# connect.net
KiCad netlist of a schematic drawn in Altium Designer
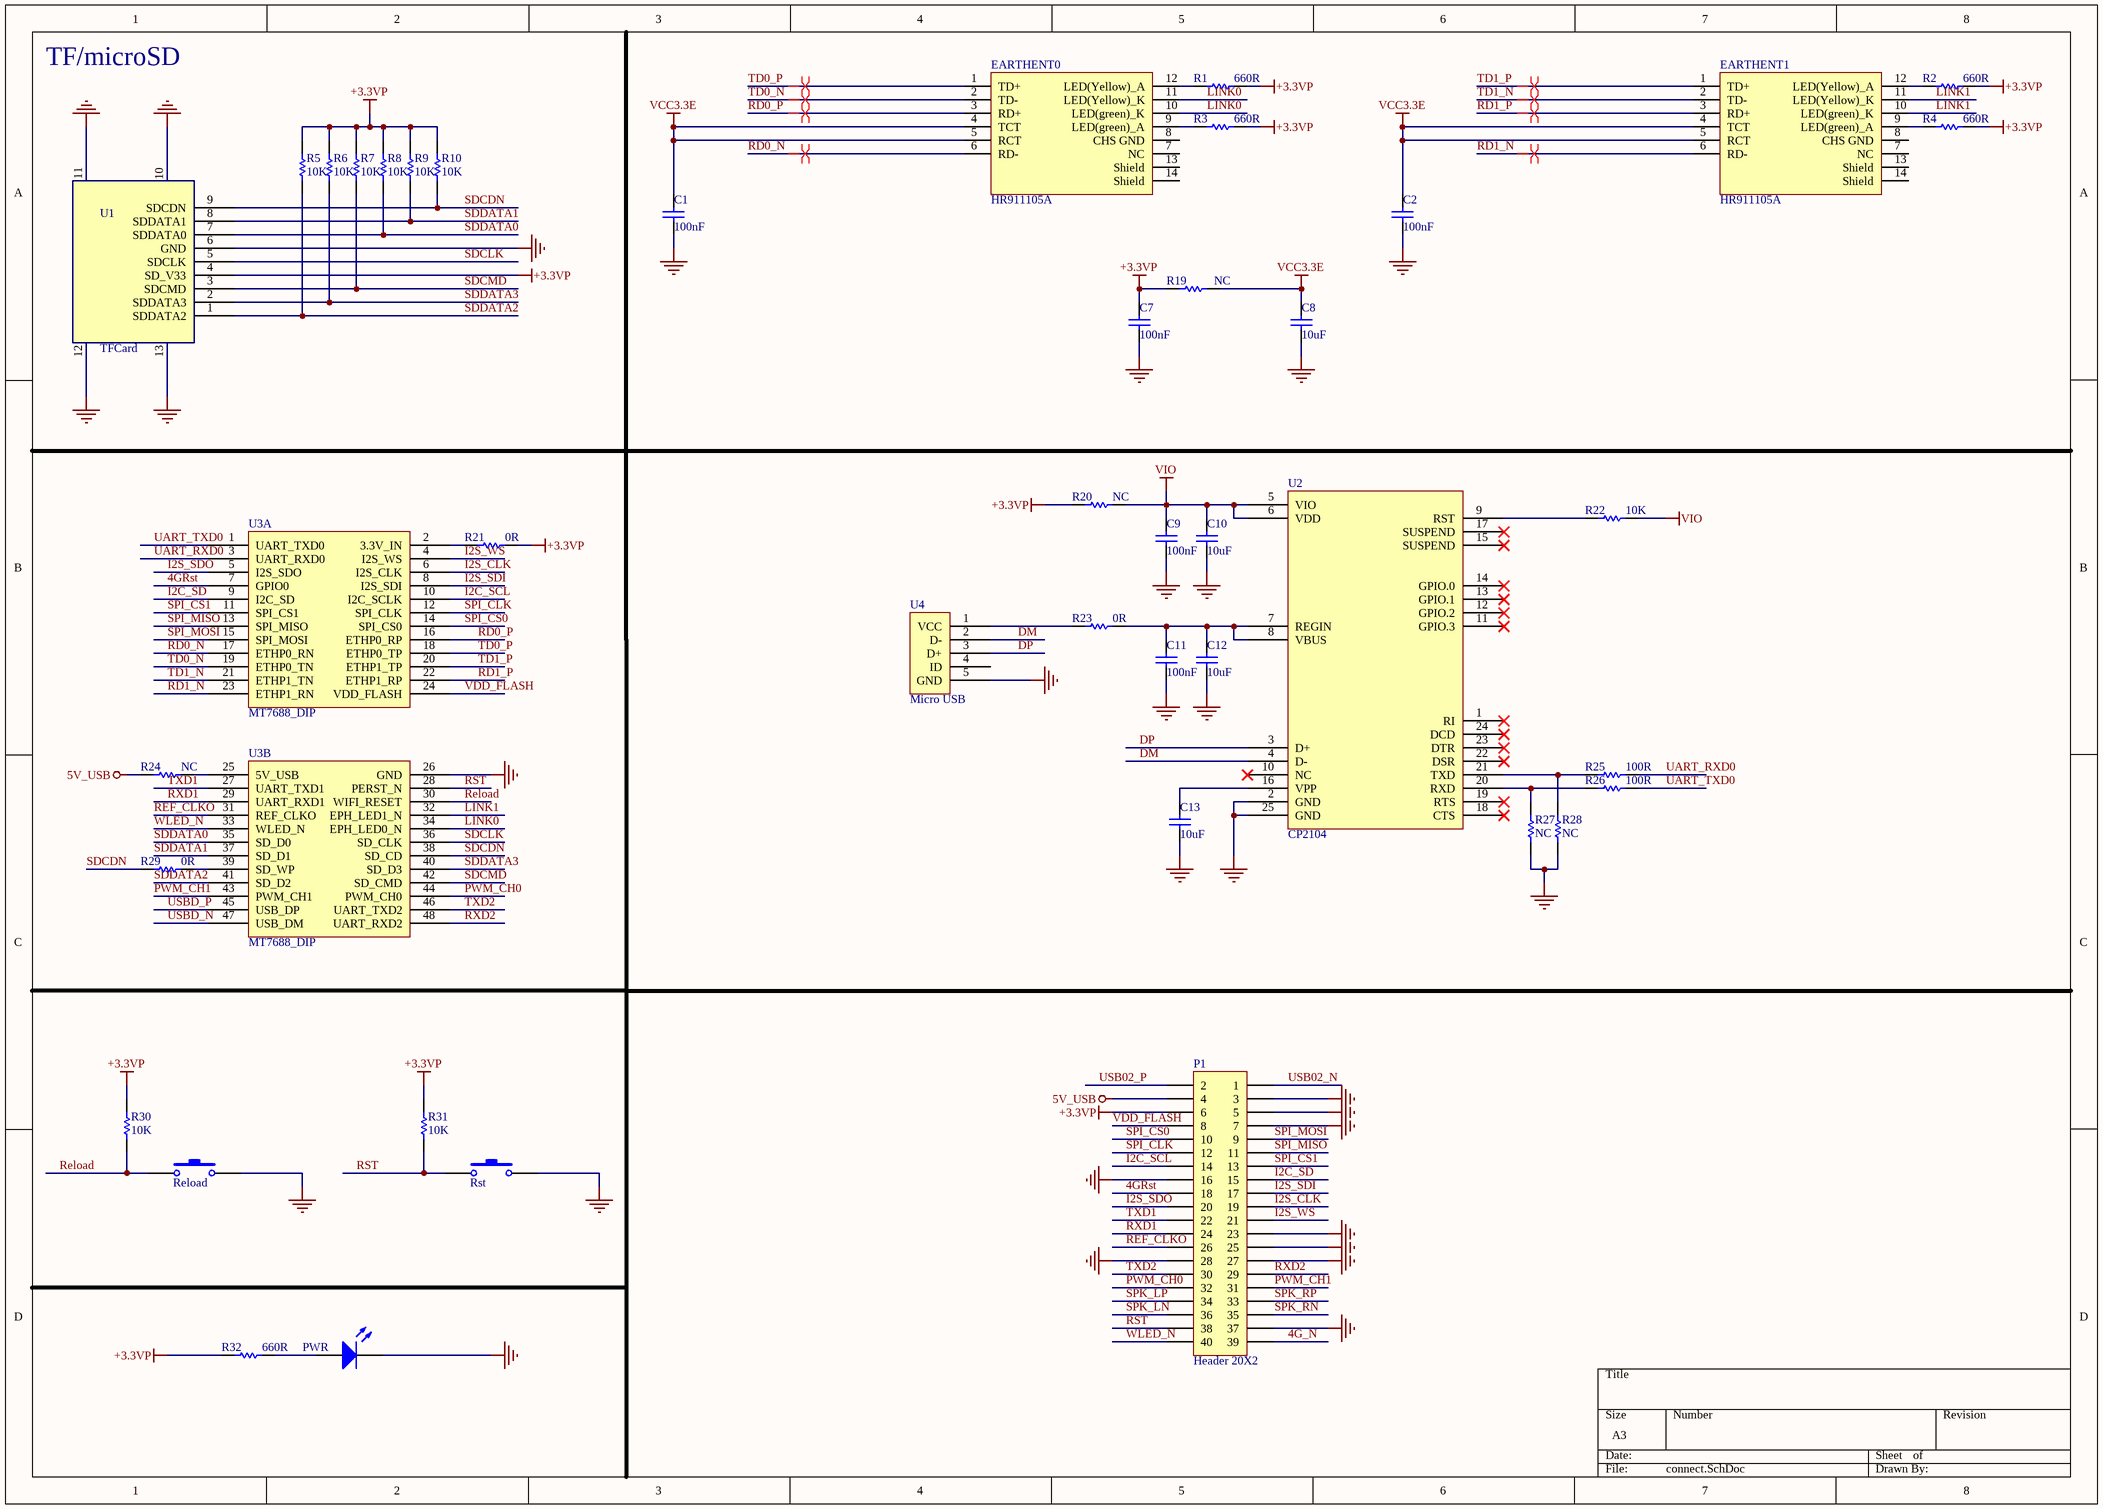
[diagram p0: connect.SchDoc]

(export (version "E")
  (design (tool "Eeschema 10.0.6"))
  (components
    (comp (ref "C1")
      (value "100nF")
      (footprint "C0603L")
      (description "Capacitor (Semiconductor SIM Model)")
      (fields (field (name "Comment") "Cap Semi") (field (name "PUBLISHER") "Altium Limited"))
      (libsource (lib "Miscellaneous Devices") (part "Cap Semi"))
    )
    (comp (ref "C2")
      (value "100nF")
      (footprint "C0603L")
      (description "Capacitor (Semiconductor SIM Model)")
      (fields (field (name "Comment") "Cap Semi") (field (name "PUBLISHER") "Altium Limited"))
      (libsource (lib "Miscellaneous Devices") (part "Cap Semi"))
    )
    (comp (ref "C7")
      (value "100nF")
      (footprint "C0603L")
      (description "Capacitor (Semiconductor SIM Model)")
      (fields (field (name "Comment") "Cap Semi") (field (name "PUBLISHER") "Altium Limited"))
      (libsource (lib "Miscellaneous Devices") (part "Cap Semi"))
    )
    (comp (ref "C8")
      (value "10uF")
      (footprint "C0603L")
      (description "Capacitor (Semiconductor SIM Model)")
      (fields (field (name "Comment") "Cap Semi") (field (name "PUBLISHER") "Altium Limited"))
      (libsource (lib "Miscellaneous Devices") (part "Cap Semi"))
    )
    (comp (ref "C9")
      (value "100nF")
      (footprint "C0603L")
      (description "Capacitor (Semiconductor SIM Model)")
      (fields (field (name "Comment") "Cap Semi") (field (name "PUBLISHER") "Altium Limited"))
      (libsource (lib "Miscellaneous Devices") (part "Cap Semi"))
    )
    (comp (ref "C10")
      (value "10uF")
      (footprint "C0603L")
      (description "Capacitor (Semiconductor SIM Model)")
      (fields (field (name "Comment") "Cap Semi") (field (name "PUBLISHER") "Altium Limited"))
      (libsource (lib "Miscellaneous Devices") (part "Cap Semi"))
    )
    (comp (ref "C11")
      (value "100nF")
      (footprint "C0603L")
      (description "Capacitor (Semiconductor SIM Model)")
      (fields (field (name "Comment") "Cap Semi") (field (name "PUBLISHER") "Altium Limited"))
      (libsource (lib "Miscellaneous Devices") (part "Cap Semi"))
    )
    (comp (ref "C12")
      (value "10uF")
      (footprint "C0603L")
      (description "Capacitor (Semiconductor SIM Model)")
      (fields (field (name "Comment") "Cap Semi") (field (name "PUBLISHER") "Altium Limited"))
      (libsource (lib "Miscellaneous Devices") (part "Cap Semi"))
    )
    (comp (ref "C13")
      (value "10uF")
      (footprint "C0603L")
      (description "Capacitor (Semiconductor SIM Model)")
      (fields (field (name "Comment") "Cap Semi") (field (name "PUBLISHER") "Altium Limited"))
      (libsource (lib "Miscellaneous Devices") (part "Cap Semi"))
    )
    (comp (ref "EARTHENT0")
      (value "HR911105A")
      (footprint "HR911105A")
      (fields (field (name "PART NUMBER") "3DZ0105115"))
      (libsource (lib "接插件") (part "HR911105A"))
    )
    (comp (ref "EARTHENT1")
      (value "HR911105A")
      (footprint "HR911105A")
      (fields (field (name "PART NUMBER") "3DZ0105115"))
      (libsource (lib "接插件") (part "HR911105A"))
    )
    (comp (ref "P1")
      (value "Header 20X2")
      (footprint "HDR2X20")
      (description "Header, 20-Pin, Dual row")
      (fields (field (name "PUBLISHER") "Altium Limited"))
      (libsource (lib "Miscellaneous Connectors") (part "Header 20X2"))
    )
    (comp (ref "PWR")
      (value "leds_0603")
      (footprint "0603LED")
      (libsource (lib "USB_SOUND") (part "leds_0603"))
    )
    (comp (ref "R1")
      (value "660R")
      (footprint "R0603L")
      (description "Semiconductor Resistor")
      (fields (field (name "Comment") "Res Semi") (field (name "PUBLISHER") "Altium Limited"))
      (libsource (lib "Miscellaneous Devices") (part "Res Semi"))
    )
    (comp (ref "R2")
      (value "660R")
      (footprint "R0603L")
      (description "Semiconductor Resistor")
      (fields (field (name "Comment") "Res Semi") (field (name "PUBLISHER") "Altium Limited"))
      (libsource (lib "Miscellaneous Devices") (part "Res Semi"))
    )
    (comp (ref "R3")
      (value "660R")
      (footprint "R0603L")
      (description "Semiconductor Resistor")
      (fields (field (name "Comment") "Res Semi") (field (name "PUBLISHER") "Altium Limited"))
      (libsource (lib "Miscellaneous Devices") (part "Res Semi"))
    )
    (comp (ref "R4")
      (value "660R")
      (footprint "R0603L")
      (description "Semiconductor Resistor")
      (fields (field (name "Comment") "Res Semi") (field (name "PUBLISHER") "Altium Limited"))
      (libsource (lib "Miscellaneous Devices") (part "Res Semi"))
    )
    (comp (ref "R5")
      (value "10K")
      (footprint "R0603L")
      (description "Semiconductor Resistor")
      (fields (field (name "Comment") "Res Semi") (field (name "PUBLISHER") "Altium Limited"))
      (libsource (lib "Miscellaneous Devices") (part "Res Semi"))
    )
    (comp (ref "R6")
      (value "10K")
      (footprint "R0603L")
      (description "Semiconductor Resistor")
      (fields (field (name "Comment") "Res Semi") (field (name "PUBLISHER") "Altium Limited"))
      (libsource (lib "Miscellaneous Devices") (part "Res Semi"))
    )
    (comp (ref "R7")
      (value "10K")
      (footprint "R0603L")
      (description "Semiconductor Resistor")
      (fields (field (name "Comment") "Res Semi") (field (name "PUBLISHER") "Altium Limited"))
      (libsource (lib "Miscellaneous Devices") (part "Res Semi"))
    )
    (comp (ref "R8")
      (value "10K")
      (footprint "R0603L")
      (description "Semiconductor Resistor")
      (fields (field (name "Comment") "Res Semi") (field (name "PUBLISHER") "Altium Limited"))
      (libsource (lib "Miscellaneous Devices") (part "Res Semi"))
    )
    (comp (ref "R9")
      (value "10K")
      (footprint "R0603L")
      (description "Semiconductor Resistor")
      (fields (field (name "Comment") "Res Semi") (field (name "PUBLISHER") "Altium Limited"))
      (libsource (lib "Miscellaneous Devices") (part "Res Semi"))
    )
    (comp (ref "R10")
      (value "10K")
      (footprint "R0603L")
      (description "Semiconductor Resistor")
      (fields (field (name "Comment") "Res Semi") (field (name "PUBLISHER") "Altium Limited"))
      (libsource (lib "Miscellaneous Devices") (part "Res Semi"))
    )
    (comp (ref "R19")
      (value "NC")
      (footprint "R0603L")
      (description "Semiconductor Resistor")
      (fields (field (name "Comment") "Res Semi") (field (name "PUBLISHER") "Altium Limited"))
      (libsource (lib "Miscellaneous Devices") (part "Res Semi"))
    )
    (comp (ref "R20")
      (value "NC")
      (footprint "R0603L")
      (description "Semiconductor Resistor")
      (fields (field (name "Comment") "Res Semi") (field (name "PUBLISHER") "Altium Limited"))
      (libsource (lib "Miscellaneous Devices") (part "Res Semi"))
    )
    (comp (ref "R21")
      (value "0R")
      (footprint "R0603L")
      (description "Semiconductor Resistor")
      (fields (field (name "Comment") "Res Semi") (field (name "PUBLISHER") "Altium Limited"))
      (libsource (lib "Miscellaneous Devices") (part "Res Semi"))
    )
    (comp (ref "R22")
      (value "10K")
      (footprint "R0603L")
      (description "Semiconductor Resistor")
      (fields (field (name "Comment") "Res Semi") (field (name "PUBLISHER") "Altium Limited"))
      (libsource (lib "Miscellaneous Devices") (part "Res Semi"))
    )
    (comp (ref "R23")
      (value "0R")
      (footprint "R0603L")
      (description "Semiconductor Resistor")
      (fields (field (name "Comment") "Res Semi") (field (name "PUBLISHER") "Altium Limited"))
      (libsource (lib "Miscellaneous Devices") (part "Res Semi"))
    )
    (comp (ref "R24")
      (value "NC")
      (footprint "R0603L")
      (description "Semiconductor Resistor")
      (fields (field (name "Comment") "Res Semi") (field (name "PUBLISHER") "Altium Limited"))
      (libsource (lib "Miscellaneous Devices") (part "Res Semi"))
    )
    (comp (ref "R25")
      (value "100R")
      (footprint "R0603L")
      (description "Semiconductor Resistor")
      (fields (field (name "Comment") "Res Semi") (field (name "PUBLISHER") "Altium Limited"))
      (libsource (lib "Miscellaneous Devices") (part "Res Semi"))
    )
    (comp (ref "R26")
      (value "100R")
      (footprint "R0603L")
      (description "Semiconductor Resistor")
      (fields (field (name "Comment") "Res Semi") (field (name "PUBLISHER") "Altium Limited"))
      (libsource (lib "Miscellaneous Devices") (part "Res Semi"))
    )
    (comp (ref "R27")
      (value "NC")
      (footprint "R0603L")
      (description "Semiconductor Resistor")
      (fields (field (name "Comment") "Res Semi") (field (name "PUBLISHER") "Altium Limited"))
      (libsource (lib "Miscellaneous Devices") (part "Res Semi"))
    )
    (comp (ref "R28")
      (value "NC")
      (footprint "R0603L")
      (description "Semiconductor Resistor")
      (fields (field (name "Comment") "Res Semi") (field (name "PUBLISHER") "Altium Limited"))
      (libsource (lib "Miscellaneous Devices") (part "Res Semi"))
    )
    (comp (ref "R29")
      (value "0R")
      (footprint "R0603L")
      (description "Semiconductor Resistor")
      (fields (field (name "Comment") "Res Semi") (field (name "PUBLISHER") "Altium Limited"))
      (libsource (lib "Miscellaneous Devices") (part "Res Semi"))
    )
    (comp (ref "R30")
      (value "10K")
      (footprint "R0603L")
      (description "Semiconductor Resistor")
      (fields (field (name "Comment") "Res Semi") (field (name "PUBLISHER") "Altium Limited"))
      (libsource (lib "Miscellaneous Devices") (part "Res Semi"))
    )
    (comp (ref "R31")
      (value "10K")
      (footprint "R0603L")
      (description "Semiconductor Resistor")
      (fields (field (name "Comment") "Res Semi") (field (name "PUBLISHER") "Altium Limited"))
      (libsource (lib "Miscellaneous Devices") (part "Res Semi"))
    )
    (comp (ref "R32")
      (value "660R")
      (footprint "R0603L")
      (description "Semiconductor Resistor")
      (fields (field (name "Comment") "Res Semi") (field (name "PUBLISHER") "Altium Limited"))
      (libsource (lib "Miscellaneous Devices") (part "Res Semi"))
    )
    (comp (ref "Reload") (value "key") (footprint "2x3SWD") (libsource (lib "USB_SOUND") (part "key")))
    (comp (ref "Rst") (value "key") (footprint "2x3SWD") (libsource (lib "USB_SOUND") (part "key")))
    (comp (ref "U1") (value "TFCard") (footprint "TFCard-1") (libsource (lib "USB_SOUND") (part "TFCard")))
    (comp (ref "U2")
      (value "CP2104")
      (footprint "QFN24_4X4")
      (libsource (lib "wooya_lib_footprint") (part "CP2104"))
    )
    (comp (ref "U3")
      (value "MT7688_DIP")
      (footprint "MT7688_DIP")
      (libsource (lib "wooya") (part "MT7688_DIP"))
    )
    (comp (ref "U4")
      (value "Micro USB")
      (footprint "USB-15B1")
      (libsource (lib "USB_SOUND") (part "USB mini-b"))
    )
  )
  (nets
    (net (code "1") (name "+3.3VP") (class "Default")
      (node (ref "C7") (pin "1") (pinfunction "1_1") (pintype "passive"))
      (node (ref "P1") (pin "6") (pinfunction "6_6") (pintype "passive"))
      (node (ref "R1") (pin "1") (pinfunction "1_1") (pintype "passive"))
      (node (ref "R10") (pin "2") (pinfunction "2_2") (pintype "passive"))
      (node (ref "R19") (pin "2") (pinfunction "2_2") (pintype "passive"))
      (node (ref "R2") (pin "1") (pinfunction "1_1") (pintype "passive"))
      (node (ref "R20") (pin "2") (pinfunction "2_2") (pintype "passive"))
      (node (ref "R21") (pin "1") (pinfunction "1_1") (pintype "passive"))
      (node (ref "R3") (pin "1") (pinfunction "1_1") (pintype "passive"))
      (node (ref "R30") (pin "2") (pinfunction "2_2") (pintype "passive"))
      (node (ref "R31") (pin "2") (pinfunction "2_2") (pintype "passive"))
      (node (ref "R32") (pin "2") (pinfunction "2_2") (pintype "passive"))
      (node (ref "R4") (pin "1") (pinfunction "1_1") (pintype "passive"))
      (node (ref "R5") (pin "2") (pinfunction "2_2") (pintype "passive"))
      (node (ref "R6") (pin "2") (pinfunction "2_2") (pintype "passive"))
      (node (ref "R7") (pin "2") (pinfunction "2_2") (pintype "passive"))
      (node (ref "R8") (pin "2") (pinfunction "2_2") (pintype "passive"))
      (node (ref "R9") (pin "2") (pinfunction "2_2") (pintype "passive"))
      (node (ref "U1") (pin "4") (pinfunction "SD_V33_4") (pintype "passive"))
    )
    (net (code "2") (name "/4GRst") (class "Default")
      (node (ref "P1") (pin "18") (pinfunction "18_18") (pintype "passive"))
      (node (ref "U3") (pin "7") (pinfunction "GPIO0_7") (pintype "passive"))
    )
    (net (code "3") (name "/4G_N") (class "Default")
      (node (ref "P1") (pin "39") (pinfunction "39_39") (pintype "passive"))
    )
    (net (code "4") (name "/DM") (class "Default")
      (node (ref "U2") (pin "4") (pinfunction "D-_4") (pintype "passive"))
      (node (ref "U4") (pin "2") (pinfunction "D-_2") (pintype "passive"))
    )
    (net (code "5") (name "/DP") (class "Default")
      (node (ref "U2") (pin "3") (pinfunction "D+_3") (pintype "passive"))
      (node (ref "U4") (pin "3") (pinfunction "D+_3") (pintype "passive"))
    )
    (net (code "6") (name "/I2C_SCL") (class "Default")
      (node (ref "P1") (pin "14") (pinfunction "14_14") (pintype "passive"))
      (node (ref "U3") (pin "10") (pinfunction "I2C_SCLK_10") (pintype "passive"))
    )
    (net (code "7") (name "/I2C_SD") (class "Default")
      (node (ref "P1") (pin "15") (pinfunction "15_15") (pintype "passive"))
      (node (ref "U3") (pin "9") (pinfunction "I2C_SD_9") (pintype "passive"))
    )
    (net (code "8") (name "/I2S_CLK") (class "Default")
      (node (ref "P1") (pin "19") (pinfunction "19_19") (pintype "passive"))
      (node (ref "U3") (pin "6") (pinfunction "I2S_CLK_6") (pintype "passive"))
    )
    (net (code "9") (name "/I2S_SDI") (class "Default")
      (node (ref "P1") (pin "17") (pinfunction "17_17") (pintype "passive"))
      (node (ref "U3") (pin "8") (pinfunction "I2S_SDI_8") (pintype "passive"))
    )
    (net (code "10") (name "/I2S_SDO") (class "Default")
      (node (ref "P1") (pin "20") (pinfunction "20_20") (pintype "passive"))
      (node (ref "U3") (pin "5") (pinfunction "I2S_SDO_5") (pintype "passive"))
    )
    (net (code "11") (name "/I2S_WS") (class "Default")
      (node (ref "P1") (pin "21") (pinfunction "21_21") (pintype "passive"))
      (node (ref "U3") (pin "4") (pinfunction "I2S_WS_4") (pintype "passive"))
    )
    (net (code "12") (name "/LINK0") (class "Default")
      (node (ref "EARTHENT0") (pin "10") (pinfunction "LED(green)_K_10") (pintype "passive"))
      (node (ref "EARTHENT0") (pin "11") (pinfunction "LED(Yellow)_K_11") (pintype "passive"))
      (node (ref "U3") (pin "34") (pinfunction "EPH_LED0_N_34") (pintype "passive"))
    )
    (net (code "13") (name "/LINK1") (class "Default")
      (node (ref "EARTHENT1") (pin "10") (pinfunction "LED(green)_K_10") (pintype "passive"))
      (node (ref "EARTHENT1") (pin "11") (pinfunction "LED(Yellow)_K_11") (pintype "passive"))
      (node (ref "U3") (pin "32") (pinfunction "EPH_LED1_N_32") (pintype "passive"))
    )
    (net (code "14") (name "/PWM_CH0") (class "Default")
      (node (ref "P1") (pin "32") (pinfunction "32_32") (pintype "passive"))
      (node (ref "U3") (pin "44") (pinfunction "PWM_CH0_44") (pintype "passive"))
    )
    (net (code "15") (name "/PWM_CH1") (class "Default")
      (node (ref "P1") (pin "31") (pinfunction "31_31") (pintype "passive"))
      (node (ref "U3") (pin "43") (pinfunction "PWM_CH1_43") (pintype "passive"))
    )
    (net (code "16") (name "/RD0_N") (class "Default")
      (node (ref "EARTHENT0") (pin "6") (pinfunction "RD-_6") (pintype "passive"))
      (node (ref "U3") (pin "17") (pinfunction "ETHP0_RN_17") (pintype "passive"))
    )
    (net (code "17") (name "/RD0_P") (class "Default")
      (node (ref "EARTHENT0") (pin "3") (pinfunction "RD+_3") (pintype "passive"))
      (node (ref "U3") (pin "16") (pinfunction "ETHP0_RP_16") (pintype "passive"))
    )
    (net (code "18") (name "/RD1_N") (class "Default")
      (node (ref "EARTHENT1") (pin "6") (pinfunction "RD-_6") (pintype "passive"))
      (node (ref "U3") (pin "23") (pinfunction "ETHP1_RN_23") (pintype "passive"))
    )
    (net (code "19") (name "/RD1_P") (class "Default")
      (node (ref "EARTHENT1") (pin "3") (pinfunction "RD+_3") (pintype "passive"))
      (node (ref "U3") (pin "22") (pinfunction "ETHP1_RP_22") (pintype "passive"))
    )
    (net (code "20") (name "/REF_CLKO") (class "Default")
      (node (ref "P1") (pin "26") (pinfunction "26_26") (pintype "passive"))
      (node (ref "U3") (pin "31") (pinfunction "REF_CLKO_31") (pintype "passive"))
    )
    (net (code "21") (name "/RST") (class "Default")
      (node (ref "P1") (pin "38") (pinfunction "38_38") (pintype "passive"))
      (node (ref "R31") (pin "1") (pinfunction "1_1") (pintype "passive"))
      (node (ref "Rst") (pin "2") (pinfunction "2_2") (pintype "passive"))
      (node (ref "U3") (pin "28") (pinfunction "PERST_N_28") (pintype "passive"))
    )
    (net (code "22") (name "/RXD1") (class "Default")
      (node (ref "P1") (pin "24") (pinfunction "24_24") (pintype "passive"))
      (node (ref "U3") (pin "29") (pinfunction "UART_RXD1_29") (pintype "passive"))
    )
    (net (code "23") (name "/RXD2") (class "Default")
      (node (ref "P1") (pin "29") (pinfunction "29_29") (pintype "passive"))
      (node (ref "U3") (pin "48") (pinfunction "UART_RXD2_48") (pintype "passive"))
    )
    (net (code "24") (name "/Reload") (class "Default")
      (node (ref "R30") (pin "1") (pinfunction "1_1") (pintype "passive"))
      (node (ref "Reload") (pin "2") (pinfunction "2_2") (pintype "passive"))
      (node (ref "U3") (pin "30") (pinfunction "WIFI_RESET_30") (pintype "passive"))
    )
    (net (code "25") (name "/SDCDN") (class "Default")
      (node (ref "R10") (pin "1") (pinfunction "1_1") (pintype "passive"))
      (node (ref "R29") (pin "2") (pinfunction "2_2") (pintype "passive"))
      (node (ref "U1") (pin "9") (pinfunction "SDCDN_9") (pintype "passive"))
      (node (ref "U3") (pin "38") (pinfunction "SD_CD_38") (pintype "passive"))
    )
    (net (code "26") (name "/SDCLK") (class "Default")
      (node (ref "U1") (pin "5") (pinfunction "SDCLK_5") (pintype "passive"))
      (node (ref "U3") (pin "36") (pinfunction "SD_CLK_36") (pintype "passive"))
    )
    (net (code "27") (name "/SDCMD") (class "Default")
      (node (ref "R7") (pin "1") (pinfunction "1_1") (pintype "passive"))
      (node (ref "U1") (pin "3") (pinfunction "SDCMD_3") (pintype "passive"))
      (node (ref "U3") (pin "42") (pinfunction "SD_CMD_42") (pintype "passive"))
    )
    (net (code "28") (name "/SDDATA0") (class "Default")
      (node (ref "R8") (pin "1") (pinfunction "1_1") (pintype "passive"))
      (node (ref "U1") (pin "7") (pinfunction "SDDATA0_7") (pintype "passive"))
      (node (ref "U3") (pin "35") (pinfunction "SD_D0_35") (pintype "passive"))
    )
    (net (code "29") (name "/SDDATA1") (class "Default")
      (node (ref "R9") (pin "1") (pinfunction "1_1") (pintype "passive"))
      (node (ref "U1") (pin "8") (pinfunction "SDDATA1_8") (pintype "passive"))
      (node (ref "U3") (pin "37") (pinfunction "SD_D1_37") (pintype "passive"))
    )
    (net (code "30") (name "/SDDATA2") (class "Default")
      (node (ref "R5") (pin "1") (pinfunction "1_1") (pintype "passive"))
      (node (ref "U1") (pin "1") (pinfunction "SDDATA2_1") (pintype "passive"))
      (node (ref "U3") (pin "41") (pinfunction "SD_D2_41") (pintype "passive"))
    )
    (net (code "31") (name "/SDDATA3") (class "Default")
      (node (ref "R6") (pin "1") (pinfunction "1_1") (pintype "passive"))
      (node (ref "U1") (pin "2") (pinfunction "SDDATA3_2") (pintype "passive"))
      (node (ref "U3") (pin "40") (pinfunction "SD_D3_40") (pintype "passive"))
    )
    (net (code "32") (name "/SPI_CLK") (class "Default")
      (node (ref "P1") (pin "12") (pinfunction "12_12") (pintype "passive"))
      (node (ref "U3") (pin "12") (pinfunction "SPI_CLK_12") (pintype "passive"))
    )
    (net (code "33") (name "/SPI_CS0") (class "Default")
      (node (ref "P1") (pin "10") (pinfunction "10_10") (pintype "passive"))
      (node (ref "U3") (pin "14") (pinfunction "SPI_CS0_14") (pintype "passive"))
    )
    (net (code "34") (name "/SPI_CS1") (class "Default")
      (node (ref "P1") (pin "13") (pinfunction "13_13") (pintype "passive"))
      (node (ref "U3") (pin "11") (pinfunction "SPI_CS1_11") (pintype "passive"))
    )
    (net (code "35") (name "/SPI_MISO") (class "Default")
      (node (ref "P1") (pin "11") (pinfunction "11_11") (pintype "passive"))
      (node (ref "U3") (pin "13") (pinfunction "SPI_MISO_13") (pintype "passive"))
    )
    (net (code "36") (name "/SPI_MOSI") (class "Default")
      (node (ref "P1") (pin "9") (pinfunction "9_9") (pintype "passive"))
      (node (ref "U3") (pin "15") (pinfunction "SPI_MOSI_15") (pintype "passive"))
    )
    (net (code "37") (name "/SPK_LN") (class "Default")
      (node (ref "P1") (pin "36") (pinfunction "36_36") (pintype "passive"))
    )
    (net (code "38") (name "/SPK_LP") (class "Default")
      (node (ref "P1") (pin "34") (pinfunction "34_34") (pintype "passive"))
    )
    (net (code "39") (name "/SPK_RN") (class "Default")
      (node (ref "P1") (pin "35") (pinfunction "35_35") (pintype "passive"))
    )
    (net (code "40") (name "/SPK_RP") (class "Default")
      (node (ref "P1") (pin "33") (pinfunction "33_33") (pintype "passive"))
    )
    (net (code "41") (name "/TD0_N") (class "Default")
      (node (ref "EARTHENT0") (pin "2") (pinfunction "TD-_2") (pintype "passive"))
      (node (ref "U3") (pin "19") (pinfunction "ETHP0_TN_19") (pintype "passive"))
    )
    (net (code "42") (name "/TD0_P") (class "Default")
      (node (ref "EARTHENT0") (pin "1") (pinfunction "TD+_1") (pintype "passive"))
      (node (ref "U3") (pin "18") (pinfunction "ETHP0_TP_18") (pintype "passive"))
    )
    (net (code "43") (name "/TD1_N") (class "Default")
      (node (ref "EARTHENT1") (pin "2") (pinfunction "TD-_2") (pintype "passive"))
      (node (ref "U3") (pin "21") (pinfunction "ETHP1_TN_21") (pintype "passive"))
    )
    (net (code "44") (name "/TD1_P") (class "Default")
      (node (ref "EARTHENT1") (pin "1") (pinfunction "TD+_1") (pintype "passive"))
      (node (ref "U3") (pin "20") (pinfunction "ETHP1_TP_20") (pintype "passive"))
    )
    (net (code "45") (name "/TXD1") (class "Default")
      (node (ref "P1") (pin "22") (pinfunction "22_22") (pintype "passive"))
      (node (ref "U3") (pin "27") (pinfunction "UART_TXD1_27") (pintype "passive"))
    )
    (net (code "46") (name "/TXD2") (class "Default")
      (node (ref "P1") (pin "30") (pinfunction "30_30") (pintype "passive"))
      (node (ref "U3") (pin "46") (pinfunction "UART_TXD2_46") (pintype "passive"))
    )
    (net (code "47") (name "/UART_RXD0") (class "Default")
      (node (ref "R25") (pin "1") (pinfunction "1_1") (pintype "passive"))
      (node (ref "U3") (pin "3") (pinfunction "UART_RXD0_3") (pintype "passive"))
    )
    (net (code "48") (name "/UART_TXD0") (class "Default")
      (node (ref "R26") (pin "1") (pinfunction "1_1") (pintype "passive"))
      (node (ref "U3") (pin "1") (pinfunction "UART_TXD0_1") (pintype "passive"))
    )
    (net (code "49") (name "/USB02_N") (class "Default")
      (node (ref "P1") (pin "1") (pinfunction "1_1") (pintype "passive"))
    )
    (net (code "50") (name "/USB02_P") (class "Default")
      (node (ref "P1") (pin "2") (pinfunction "2_2") (pintype "passive"))
    )
    (net (code "51") (name "/USBD_N") (class "Default")
      (node (ref "U3") (pin "47") (pinfunction "USB_DM_47") (pintype "passive"))
    )
    (net (code "52") (name "/USBD_P") (class "Default")
      (node (ref "U3") (pin "45") (pinfunction "USB_DP_45") (pintype "passive"))
    )
    (net (code "53") (name "/VDD_FLASH") (class "Default")
      (node (ref "P1") (pin "8") (pinfunction "8_8") (pintype "passive"))
      (node (ref "U3") (pin "24") (pinfunction "VDD_FLASH_24") (pintype "passive"))
    )
    (net (code "54") (name "/WLED_N") (class "Default")
      (node (ref "P1") (pin "40") (pinfunction "40_40") (pintype "passive"))
      (node (ref "U3") (pin "33") (pinfunction "WLED_N_33") (pintype "passive"))
    )
    (net (code "55") (name "5V_USB") (class "Default")
      (node (ref "P1") (pin "4") (pinfunction "4_4") (pintype "passive"))
      (node (ref "R24") (pin "2") (pinfunction "2_2") (pintype "passive"))
    )
    (net (code "56") (name "GND") (class "Default")
      (node (ref "C1") (pin "2") (pinfunction "2_2") (pintype "passive"))
      (node (ref "C10") (pin "2") (pinfunction "2_2") (pintype "passive"))
      (node (ref "C11") (pin "2") (pinfunction "2_2") (pintype "passive"))
      (node (ref "C12") (pin "2") (pinfunction "2_2") (pintype "passive"))
      (node (ref "C13") (pin "2") (pinfunction "2_2") (pintype "passive"))
      (node (ref "C2") (pin "2") (pinfunction "2_2") (pintype "passive"))
      (node (ref "C7") (pin "2") (pinfunction "2_2") (pintype "passive"))
      (node (ref "C8") (pin "2") (pinfunction "2_2") (pintype "passive"))
      (node (ref "C9") (pin "2") (pinfunction "2_2") (pintype "passive"))
      (node (ref "P1") (pin "16") (pinfunction "16_16") (pintype "passive"))
      (node (ref "P1") (pin "23") (pinfunction "23_23") (pintype "passive"))
      (node (ref "P1") (pin "25") (pinfunction "25_25") (pintype "passive"))
      (node (ref "P1") (pin "27") (pinfunction "27_27") (pintype "passive"))
      (node (ref "P1") (pin "28") (pinfunction "28_28") (pintype "passive"))
      (node (ref "P1") (pin "3") (pinfunction "3_3") (pintype "passive"))
      (node (ref "P1") (pin "37") (pinfunction "37_37") (pintype "passive"))
      (node (ref "P1") (pin "5") (pinfunction "5_5") (pintype "passive"))
      (node (ref "P1") (pin "7") (pinfunction "7_7") (pintype "passive"))
      (node (ref "PWR") (pin "2") (pinfunction "K_2") (pintype "passive"))
      (node (ref "R27") (pin "2") (pinfunction "2_2") (pintype "passive"))
      (node (ref "R28") (pin "2") (pinfunction "2_2") (pintype "passive"))
      (node (ref "Reload") (pin "1") (pinfunction "1_1") (pintype "passive"))
      (node (ref "Rst") (pin "1") (pinfunction "1_1") (pintype "passive"))
      (node (ref "U1") (pin "10") (pinfunction "10_10") (pintype "passive"))
      (node (ref "U1") (pin "11") (pinfunction "11_11") (pintype "passive"))
      (node (ref "U1") (pin "12") (pinfunction "12_12") (pintype "passive"))
      (node (ref "U1") (pin "13") (pinfunction "13_13") (pintype "passive"))
      (node (ref "U1") (pin "6") (pinfunction "GND_6") (pintype "passive"))
      (node (ref "U2") (pin "2") (pinfunction "GND_2") (pintype "passive"))
      (node (ref "U2") (pin "25") (pinfunction "GND_25") (pintype "passive"))
      (node (ref "U3") (pin "26") (pinfunction "GND_26") (pintype "passive"))
      (node (ref "U4") (pin "5") (pinfunction "GND_5") (pintype "passive"))
    )
    (net (code "57") (name "Net-(EARTHENT0-LED(Yellow)_A)") (class "Default")
      (node (ref "EARTHENT0") (pin "12") (pinfunction "LED(Yellow)_A_12") (pintype "passive"))
      (node (ref "R1") (pin "2") (pinfunction "2_2") (pintype "passive"))
    )
    (net (code "58") (name "Net-(EARTHENT0-LED(green)_A)") (class "Default")
      (node (ref "EARTHENT0") (pin "9") (pinfunction "LED(green)_A_9") (pintype "passive"))
      (node (ref "R3") (pin "2") (pinfunction "2_2") (pintype "passive"))
    )
    (net (code "59") (name "Net-(EARTHENT1-LED(Yellow)_A)") (class "Default")
      (node (ref "EARTHENT1") (pin "12") (pinfunction "LED(Yellow)_A_12") (pintype "passive"))
      (node (ref "R2") (pin "2") (pinfunction "2_2") (pintype "passive"))
    )
    (net (code "60") (name "Net-(EARTHENT1-LED(green)_A)") (class "Default")
      (node (ref "EARTHENT1") (pin "9") (pinfunction "LED(green)_A_9") (pintype "passive"))
      (node (ref "R4") (pin "2") (pinfunction "2_2") (pintype "passive"))
    )
    (net (code "61") (name "Net-(PWR-A)") (class "Default")
      (node (ref "PWR") (pin "1") (pinfunction "A_1") (pintype "passive"))
      (node (ref "R32") (pin "1") (pinfunction "1_1") (pintype "passive"))
    )
    (net (code "62") (name "Net-(U2-REGIN)") (class "Default")
      (node (ref "C11") (pin "1") (pinfunction "1_1") (pintype "passive"))
      (node (ref "C12") (pin "1") (pinfunction "1_1") (pintype "passive"))
      (node (ref "R23") (pin "1") (pinfunction "1_1") (pintype "passive"))
      (node (ref "U2") (pin "7") (pinfunction "REGIN_7") (pintype "passive"))
      (node (ref "U2") (pin "8") (pinfunction "VBUS_8") (pintype "passive"))
    )
    (net (code "63") (name "Net-(U2-RST)") (class "Default")
      (node (ref "R22") (pin "2") (pinfunction "2_2") (pintype "passive"))
      (node (ref "U2") (pin "9") (pinfunction "RST_9") (pintype "passive"))
    )
    (net (code "64") (name "Net-(U2-RXD)") (class "Default")
      (node (ref "R26") (pin "2") (pinfunction "2_2") (pintype "passive"))
      (node (ref "R27") (pin "1") (pinfunction "1_1") (pintype "passive"))
      (node (ref "U2") (pin "20") (pinfunction "RXD_20") (pintype "passive"))
    )
    (net (code "65") (name "Net-(U2-TXD)") (class "Default")
      (node (ref "R25") (pin "2") (pinfunction "2_2") (pintype "passive"))
      (node (ref "R28") (pin "1") (pinfunction "1_1") (pintype "passive"))
      (node (ref "U2") (pin "21") (pinfunction "TXD_21") (pintype "passive"))
    )
    (net (code "66") (name "Net-(U2-VPP)") (class "Default")
      (node (ref "C13") (pin "1") (pinfunction "1_1") (pintype "passive"))
      (node (ref "U2") (pin "16") (pinfunction "VPP_16") (pintype "passive"))
    )
    (net (code "67") (name "Net-(U3A-3.3V_IN)") (class "Default")
      (node (ref "R21") (pin "2") (pinfunction "2_2") (pintype "passive"))
      (node (ref "U3") (pin "2") (pinfunction "3.3V_IN_2") (pintype "passive"))
    )
    (net (code "68") (name "Net-(U3B-5V_USB)") (class "Default")
      (node (ref "R24") (pin "1") (pinfunction "1_1") (pintype "passive"))
      (node (ref "U3") (pin "25") (pinfunction "5V_USB_25") (pintype "passive"))
    )
    (net (code "69") (name "Net-(U3B-SD_WP)") (class "Default")
      (node (ref "R29") (pin "1") (pinfunction "1_1") (pintype "passive"))
      (node (ref "U3") (pin "39") (pinfunction "SD_WP_39") (pintype "passive"))
    )
    (net (code "70") (name "Net-(U4-VCC)") (class "Default")
      (node (ref "R23") (pin "2") (pinfunction "2_2") (pintype "passive"))
      (node (ref "U4") (pin "1") (pinfunction "VCC_1") (pintype "passive"))
    )
    (net (code "71") (name "VCC3.3E") (class "Default")
      (node (ref "C1") (pin "1") (pinfunction "1_1") (pintype "passive"))
      (node (ref "C2") (pin "1") (pinfunction "1_1") (pintype "passive"))
      (node (ref "C8") (pin "1") (pinfunction "1_1") (pintype "passive"))
      (node (ref "EARTHENT0") (pin "4") (pinfunction "TCT_4") (pintype "passive"))
      (node (ref "EARTHENT0") (pin "5") (pinfunction "RCT_5") (pintype "passive"))
      (node (ref "EARTHENT1") (pin "4") (pinfunction "TCT_4") (pintype "passive"))
      (node (ref "EARTHENT1") (pin "5") (pinfunction "RCT_5") (pintype "passive"))
      (node (ref "R19") (pin "1") (pinfunction "1_1") (pintype "passive"))
    )
    (net (code "72") (name "VIO") (class "Default")
      (node (ref "C10") (pin "1") (pinfunction "1_1") (pintype "passive"))
      (node (ref "C9") (pin "1") (pinfunction "1_1") (pintype "passive"))
      (node (ref "R20") (pin "1") (pinfunction "1_1") (pintype "passive"))
      (node (ref "R22") (pin "1") (pinfunction "1_1") (pintype "passive"))
      (node (ref "U2") (pin "5") (pinfunction "VIO_5") (pintype "passive"))
      (node (ref "U2") (pin "6") (pinfunction "VDD_6") (pintype "passive"))
    )
    (net (code "73") (name "unconnected-(EARTHENT0-CHS_GND-Pad8)") (class "Default")
      (node (ref "EARTHENT0") (pin "8") (pinfunction "CHS_GND_8") (pintype "passive"))
    )
    (net (code "74") (name "unconnected-(EARTHENT0-NC-Pad7)") (class "Default")
      (node (ref "EARTHENT0") (pin "7") (pinfunction "NC_7") (pintype "passive"))
    )
    (net (code "75") (name "unconnected-(EARTHENT0-Shield-Pad13)") (class "Default")
      (node (ref "EARTHENT0") (pin "13") (pinfunction "Shield_13") (pintype "passive"))
    )
    (net (code "76") (name "unconnected-(EARTHENT0-Shield-Pad14)") (class "Default")
      (node (ref "EARTHENT0") (pin "14") (pinfunction "Shield_14") (pintype "passive"))
    )
    (net (code "77") (name "unconnected-(EARTHENT1-CHS_GND-Pad8)") (class "Default")
      (node (ref "EARTHENT1") (pin "8") (pinfunction "CHS_GND_8") (pintype "passive"))
    )
    (net (code "78") (name "unconnected-(EARTHENT1-NC-Pad7)") (class "Default")
      (node (ref "EARTHENT1") (pin "7") (pinfunction "NC_7") (pintype "passive"))
    )
    (net (code "79") (name "unconnected-(EARTHENT1-Shield-Pad13)") (class "Default")
      (node (ref "EARTHENT1") (pin "13") (pinfunction "Shield_13") (pintype "passive"))
    )
    (net (code "80") (name "unconnected-(EARTHENT1-Shield-Pad14)") (class "Default")
      (node (ref "EARTHENT1") (pin "14") (pinfunction "Shield_14") (pintype "passive"))
    )
    (net (code "81") (name "unconnected-(U2-CTS-Pad18)") (class "Default")
      (node (ref "U2") (pin "18") (pinfunction "CTS_18") (pintype "passive+no_connect"))
    )
    (net (code "82") (name "unconnected-(U2-DCD-Pad24)") (class "Default")
      (node (ref "U2") (pin "24") (pinfunction "DCD_24") (pintype "passive+no_connect"))
    )
    (net (code "83") (name "unconnected-(U2-DSR-Pad22)") (class "Default")
      (node (ref "U2") (pin "22") (pinfunction "DSR_22") (pintype "passive+no_connect"))
    )
    (net (code "84") (name "unconnected-(U2-DTR-Pad23)") (class "Default")
      (node (ref "U2") (pin "23") (pinfunction "DTR_23") (pintype "passive+no_connect"))
    )
    (net (code "85") (name "unconnected-(U2-GPIO.0-Pad14)") (class "Default")
      (node (ref "U2") (pin "14") (pinfunction "GPIO.0_14") (pintype "passive+no_connect"))
    )
    (net (code "86") (name "unconnected-(U2-GPIO.1-Pad13)") (class "Default")
      (node (ref "U2") (pin "13") (pinfunction "GPIO.1_13") (pintype "passive+no_connect"))
    )
    (net (code "87") (name "unconnected-(U2-GPIO.2-Pad12)") (class "Default")
      (node (ref "U2") (pin "12") (pinfunction "GPIO.2_12") (pintype "passive+no_connect"))
    )
    (net (code "88") (name "unconnected-(U2-GPIO.3-Pad11)") (class "Default")
      (node (ref "U2") (pin "11") (pinfunction "GPIO.3_11") (pintype "passive+no_connect"))
    )
    (net (code "89") (name "unconnected-(U2-NC-Pad10)") (class "Default")
      (node (ref "U2") (pin "10") (pinfunction "NC_10") (pintype "passive+no_connect"))
    )
    (net (code "90") (name "unconnected-(U2-RI-Pad1)") (class "Default")
      (node (ref "U2") (pin "1") (pinfunction "RI_1") (pintype "passive+no_connect"))
    )
    (net (code "91") (name "unconnected-(U2-RTS-Pad19)") (class "Default")
      (node (ref "U2") (pin "19") (pinfunction "RTS_19") (pintype "passive+no_connect"))
    )
    (net (code "92") (name "unconnected-(U2-SUSPEND-Pad15)") (class "Default")
      (node (ref "U2") (pin "15") (pinfunction "SUSPEND_15") (pintype "passive+no_connect"))
    )
    (net (code "93") (name "unconnected-(U2-SUSPEND-Pad17)") (class "Default")
      (node (ref "U2") (pin "17") (pinfunction "SUSPEND_17") (pintype "passive+no_connect"))
    )
    (net (code "94") (name "unconnected-(U4-ID-Pad4)") (class "Default")
      (node (ref "U4") (pin "4") (pinfunction "ID_4") (pintype "passive"))
    )
  )
)
